# mainboard-augmented-thermostat-v1.net
KiCad netlist of a schematic drawn in EAGLE
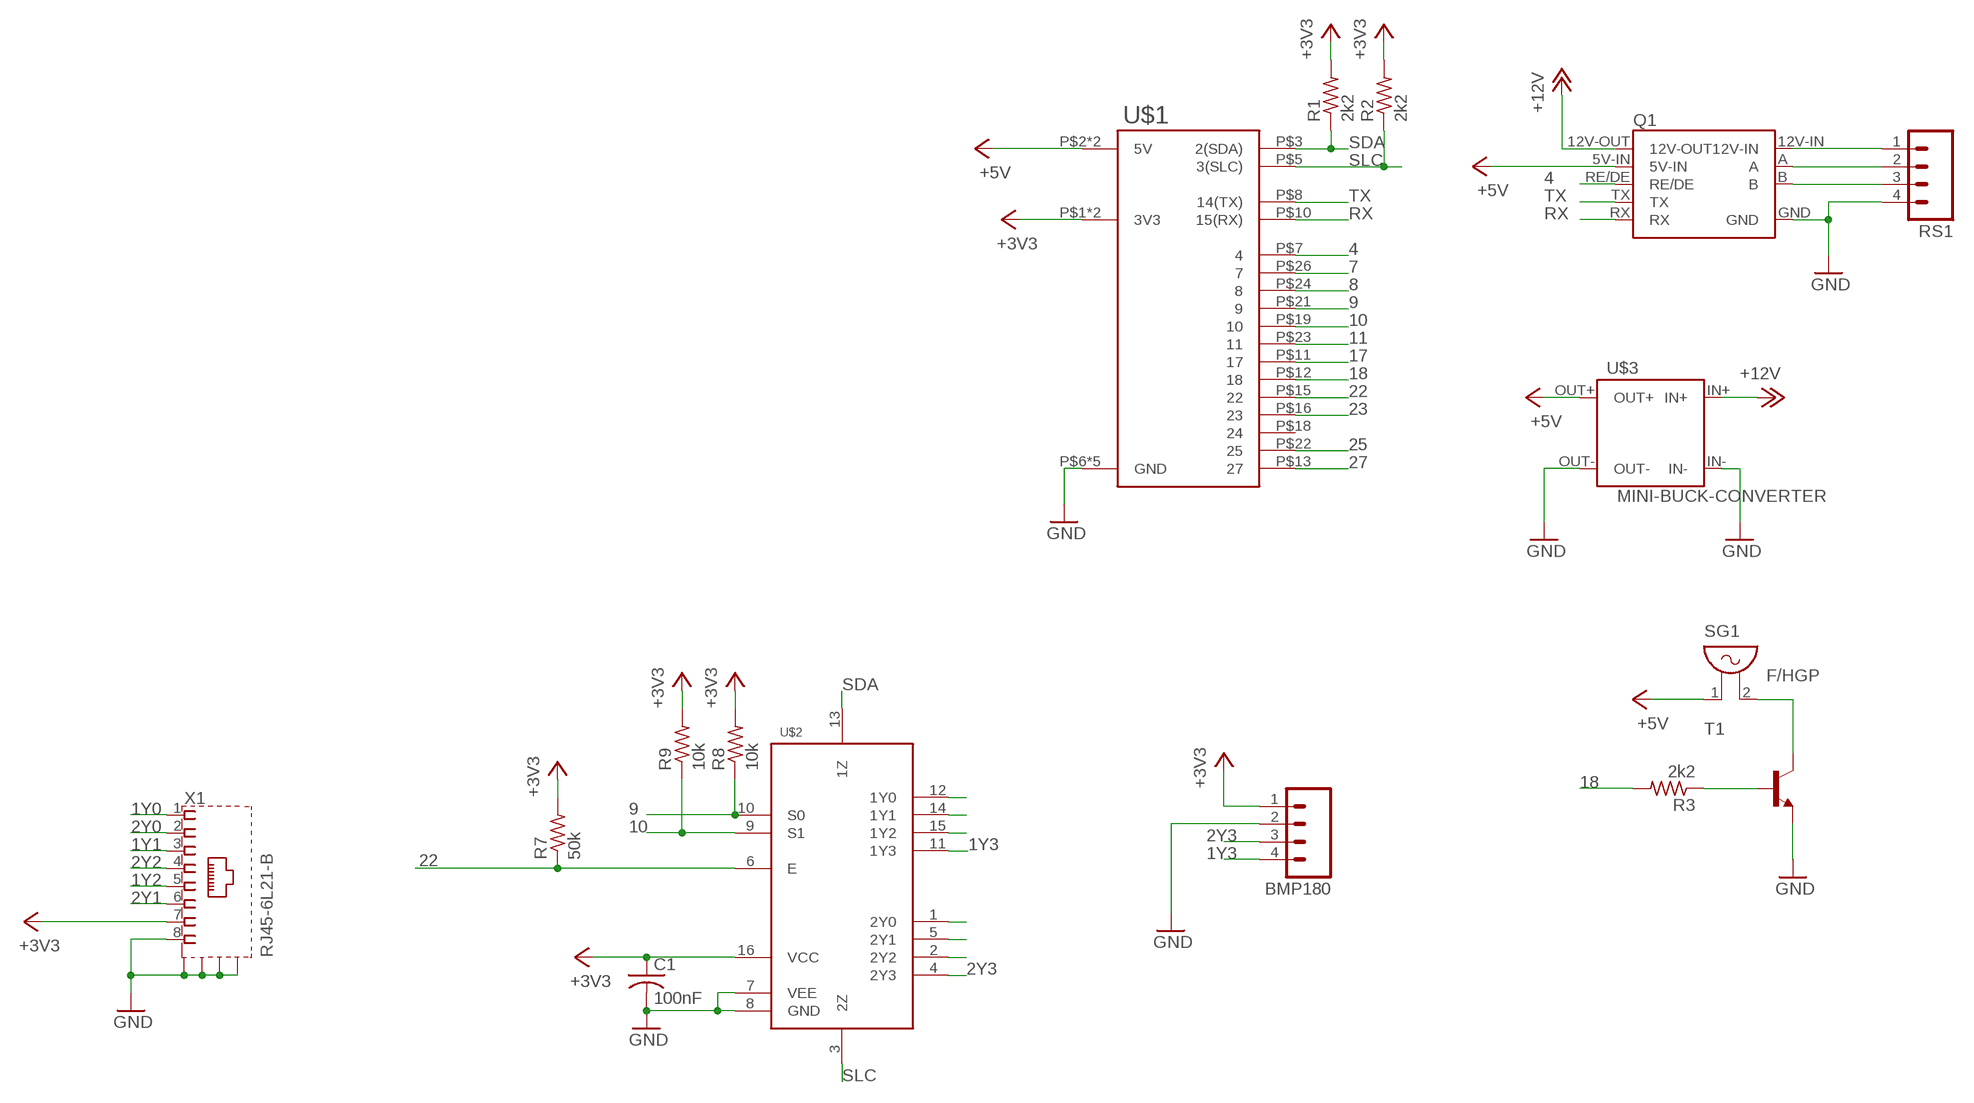
[diagram p0: schematic, sheet 1]

(export (version "E")
  (design (tool "Eeschema 10.0.6"))
  (components
    (comp (ref "BMP180")
      (value "M04")
      (footprint "eagle-import:04P")
      (libsource (lib "eagle-import") (part "M04"))
    )
    (comp (ref "C1")
      (value "100nF")
      (footprint "eagle-import:C0603K")
      (libsource (lib "eagle-import") (part "C-USC0603K"))
    )
    (comp (ref "Q1")
      (value "RS485-ADAPTER0.05-CONNECTOR")
      (footprint "eagle-import:RS485-ADAPTOR-05")
      (libsource (lib "eagle-import") (part "RS485-ADAPTER0.05-CONNECTOR"))
    )
    (comp (ref "R1")
      (value "2k2")
      (footprint "eagle-import:R0603")
      (libsource (lib "eagle-import") (part "R-US_R0603"))
    )
    (comp (ref "R2")
      (value "2k2")
      (footprint "eagle-import:R0603")
      (libsource (lib "eagle-import") (part "R-US_R0603"))
    )
    (comp (ref "R3")
      (value "2k2")
      (footprint "eagle-import:R0603")
      (libsource (lib "eagle-import") (part "R-US_R0603"))
    )
    (comp (ref "R7")
      (value "50k")
      (footprint "eagle-import:R0603")
      (libsource (lib "eagle-import") (part "R-US_R0603"))
    )
    (comp (ref "R8")
      (value "10k")
      (footprint "eagle-import:R0603")
      (libsource (lib "eagle-import") (part "R-US_R0603"))
    )
    (comp (ref "R9")
      (value "10k")
      (footprint "eagle-import:R0603")
      (libsource (lib "eagle-import") (part "R-US_R0603"))
    )
    (comp (ref "RS1")
      (value "M04")
      (footprint "eagle-import:04P")
      (libsource (lib "eagle-import") (part "M04"))
    )
    (comp (ref "SG1")
      (value "F/HGP")
      (footprint "eagle-import:F_HGP")
      (libsource (lib "eagle-import") (part "F/HGP"))
    )
    (comp (ref "T1")
      (value "BC808-NPN-SOT23-BEC")
      (footprint "eagle-import:SOT23-BEC")
      (libsource (lib "eagle-import") (part "-NPN-SOT23-BECBC808"))
    )
    (comp (ref "U$1")
      (value "RASPI-GPIO")
      (footprint "eagle-import:RASPI-GPIO-1")
      (libsource (lib "eagle-import") (part "RASPI-GPIO"))
    )
    (comp (ref "U$2")
      (value "74HC4052SO-16")
      (footprint "eagle-import:SO16")
      (libsource (lib "eagle-import") (part "74HC4052SO-16"))
    )
    (comp (ref "U$3")
      (value "MINI-BUCK-CONVERTER")
      (footprint "eagle-import:MINI-BUCK-CONVERTER")
      (libsource (lib "eagle-import") (part "MINI-BUCK-CONVERTER"))
    )
    (comp (ref "X1")
      (value "RJ45-6L21-B")
      (footprint "eagle-import:RJ45-SHIELD1")
      (libsource (lib "eagle-import") (part "RJ4521-B-6L"))
    )
  )
  (nets
    (net (code "1") (name "+3V3") (class "Default")
      (node (ref "BMP180") (pin "1") (pinfunction "1_1") (pintype "passive"))
      (node (ref "C1") (pin "1") (pinfunction "1_1") (pintype "passive"))
      (node (ref "R1") (pin "2") (pinfunction "2_2") (pintype "passive"))
      (node (ref "R2") (pin "2") (pinfunction "2_2") (pintype "passive"))
      (node (ref "R7") (pin "2") (pinfunction "2_2") (pintype "passive"))
      (node (ref "R8") (pin "2") (pinfunction "2_2") (pintype "passive"))
      (node (ref "R9") (pin "2") (pinfunction "2_2") (pintype "passive"))
      (node (ref "U$1") (pin "P$1") (pinfunction "3V3_P$1") (pintype "power_in"))
      (node (ref "U$1") (pin "P$17") (pinfunction "3V3_P$17") (pintype "power_in"))
      (node (ref "U$2") (pin "16") (pinfunction "VCC_16") (pintype "power_in"))
      (node (ref "X1") (pin "7") (pinfunction "7_7") (pintype "passive"))
    )
    (net (code "2") (name "+5V") (class "Default")
      (node (ref "Q1") (pin "5V-IN") (pinfunction "5V-IN_5V-IN") (pintype "power_in"))
      (node (ref "SG1") (pin "1") (pinfunction "1_1") (pintype "passive"))
      (node (ref "U$1") (pin "P$2") (pinfunction "5V_P$2") (pintype "power_in"))
      (node (ref "U$1") (pin "P$4") (pinfunction "5V_P$4") (pintype "power_in"))
      (node (ref "U$3") (pin "OUT+") (pinfunction "OUT+_OUT+") (pintype "power_in"))
    )
    (net (code "3") (name "+12V") (class "Default")
      (node (ref "Q1") (pin "12V-OUT") (pinfunction "12V-OUT_12V-OUT") (pintype "power_in"))
      (node (ref "U$3") (pin "IN+") (pinfunction "IN+_IN+") (pintype "power_in"))
    )
    (net (code "4") (name "/1Y0") (class "Default")
      (node (ref "U$2") (pin "12") (pinfunction "1Y0_12") (pintype "bidirectional"))
      (node (ref "X1") (pin "1") (pinfunction "1_1") (pintype "passive"))
    )
    (net (code "5") (name "/1Y1") (class "Default")
      (node (ref "U$2") (pin "14") (pinfunction "1Y1_14") (pintype "bidirectional"))
      (node (ref "X1") (pin "3") (pinfunction "3_3") (pintype "passive"))
    )
    (net (code "6") (name "/1Y2") (class "Default")
      (node (ref "U$2") (pin "15") (pinfunction "1Y2_15") (pintype "bidirectional"))
      (node (ref "X1") (pin "5") (pinfunction "5_5") (pintype "passive"))
    )
    (net (code "7") (name "/1Y3") (class "Default")
      (node (ref "BMP180") (pin "4") (pinfunction "4_4") (pintype "passive"))
      (node (ref "U$2") (pin "11") (pinfunction "1Y3_11") (pintype "bidirectional"))
    )
    (net (code "8") (name "/2Y0") (class "Default")
      (node (ref "U$2") (pin "1") (pinfunction "2Y0_1") (pintype "bidirectional"))
      (node (ref "X1") (pin "2") (pinfunction "2_2") (pintype "passive"))
    )
    (net (code "9") (name "/2Y1") (class "Default")
      (node (ref "U$2") (pin "5") (pinfunction "2Y1_5") (pintype "bidirectional"))
      (node (ref "X1") (pin "6") (pinfunction "6_6") (pintype "passive"))
    )
    (net (code "10") (name "/2Y2") (class "Default")
      (node (ref "U$2") (pin "2") (pinfunction "2Y2_2") (pintype "bidirectional"))
      (node (ref "X1") (pin "4") (pinfunction "4_4") (pintype "passive"))
    )
    (net (code "11") (name "/2Y3") (class "Default")
      (node (ref "BMP180") (pin "3") (pinfunction "3_3") (pintype "passive"))
      (node (ref "U$2") (pin "4") (pinfunction "2Y3_4") (pintype "bidirectional"))
    )
    (net (code "12") (name "/4") (class "Default")
      (node (ref "Q1") (pin "RE/DE") (pinfunction "RE/DE_RE/DE") (pintype "bidirectional"))
      (node (ref "U$1") (pin "P$7") (pinfunction "4_P$7") (pintype "bidirectional"))
    )
    (net (code "13") (name "/7") (class "Default")
      (node (ref "U$1") (pin "P$26") (pinfunction "7_P$26") (pintype "bidirectional"))
    )
    (net (code "14") (name "/8") (class "Default")
      (node (ref "U$1") (pin "P$24") (pinfunction "8_P$24") (pintype "bidirectional"))
    )
    (net (code "15") (name "/9") (class "Default")
      (node (ref "R8") (pin "1") (pinfunction "1_1") (pintype "passive"))
      (node (ref "U$1") (pin "P$21") (pinfunction "9_P$21") (pintype "bidirectional"))
      (node (ref "U$2") (pin "10") (pinfunction "S0_10") (pintype "bidirectional"))
    )
    (net (code "16") (name "/10") (class "Default")
      (node (ref "R9") (pin "1") (pinfunction "1_1") (pintype "passive"))
      (node (ref "U$1") (pin "P$19") (pinfunction "10_P$19") (pintype "bidirectional"))
      (node (ref "U$2") (pin "9") (pinfunction "S1_9") (pintype "bidirectional"))
    )
    (net (code "17") (name "/11") (class "Default")
      (node (ref "U$1") (pin "P$23") (pinfunction "11_P$23") (pintype "bidirectional"))
    )
    (net (code "18") (name "/17") (class "Default")
      (node (ref "U$1") (pin "P$11") (pinfunction "17_P$11") (pintype "bidirectional"))
    )
    (net (code "19") (name "/18") (class "Default")
      (node (ref "R3") (pin "2") (pinfunction "2_2") (pintype "passive"))
      (node (ref "U$1") (pin "P$12") (pinfunction "18_P$12") (pintype "bidirectional"))
    )
    (net (code "20") (name "/22") (class "Default")
      (node (ref "R7") (pin "1") (pinfunction "1_1") (pintype "passive"))
      (node (ref "U$1") (pin "P$15") (pinfunction "22_P$15") (pintype "bidirectional"))
      (node (ref "U$2") (pin "6") (pinfunction "E_6") (pintype "bidirectional"))
    )
    (net (code "21") (name "/23") (class "Default")
      (node (ref "U$1") (pin "P$16") (pinfunction "23_P$16") (pintype "bidirectional"))
    )
    (net (code "22") (name "/25") (class "Default")
      (node (ref "U$1") (pin "P$22") (pinfunction "25_P$22") (pintype "bidirectional"))
    )
    (net (code "23") (name "/27") (class "Default")
      (node (ref "U$1") (pin "P$13") (pinfunction "27_P$13") (pintype "bidirectional"))
    )
    (net (code "24") (name "/RX") (class "Default")
      (node (ref "Q1") (pin "RX") (pinfunction "RX_RX") (pintype "bidirectional"))
      (node (ref "U$1") (pin "P$10") (pinfunction "15(RX)_P$10") (pintype "bidirectional"))
    )
    (net (code "25") (name "/SDA") (class "Default")
      (node (ref "R1") (pin "1") (pinfunction "1_1") (pintype "passive"))
      (node (ref "U$1") (pin "P$3") (pinfunction "2(SDA)_P$3") (pintype "bidirectional"))
      (node (ref "U$2") (pin "13") (pinfunction "1Z_13") (pintype "input"))
    )
    (net (code "26") (name "/SLC") (class "Default")
      (node (ref "R2") (pin "1") (pinfunction "1_1") (pintype "passive"))
      (node (ref "U$1") (pin "P$5") (pinfunction "3(SLC)_P$5") (pintype "bidirectional"))
      (node (ref "U$2") (pin "3") (pinfunction "2Z_3") (pintype "output"))
    )
    (net (code "27") (name "/TX") (class "Default")
      (node (ref "Q1") (pin "TX") (pinfunction "TX_TX") (pintype "bidirectional"))
      (node (ref "U$1") (pin "P$8") (pinfunction "14(TX)_P$8") (pintype "bidirectional"))
    )
    (net (code "28") (name "GND") (class "Default")
      (node (ref "BMP180") (pin "2") (pinfunction "2_2") (pintype "passive"))
      (node (ref "C1") (pin "2") (pinfunction "2_2") (pintype "passive"))
      (node (ref "Q1") (pin "GND") (pinfunction "GND_GND") (pintype "power_in"))
      (node (ref "RS1") (pin "4") (pinfunction "4_4") (pintype "passive"))
      (node (ref "T1") (pin "E") (pinfunction "E_E") (pintype "passive"))
      (node (ref "U$1") (pin "P$14") (pinfunction "GND_P$14") (pintype "power_in"))
      (node (ref "U$1") (pin "P$20") (pinfunction "GND_P$20") (pintype "power_in"))
      (node (ref "U$1") (pin "P$25") (pinfunction "GND_P$25") (pintype "power_in"))
      (node (ref "U$1") (pin "P$6") (pinfunction "GND_P$6") (pintype "power_in"))
      (node (ref "U$1") (pin "P$9") (pinfunction "GND_P$9") (pintype "power_in"))
      (node (ref "U$2") (pin "7") (pinfunction "VEE_7") (pintype "power_in"))
      (node (ref "U$2") (pin "8") (pinfunction "GND_8") (pintype "power_in"))
      (node (ref "U$3") (pin "IN-") (pinfunction "IN-_IN-") (pintype "power_in"))
      (node (ref "U$3") (pin "OUT-") (pinfunction "OUT-_OUT-") (pintype "power_in"))
      (node (ref "X1") (pin "8") (pinfunction "8_8") (pintype "passive"))
      (node (ref "X1") (pin "S1") (pinfunction "S_S1") (pintype "passive"))
      (node (ref "X1") (pin "S2") (pinfunction "S_S2") (pintype "passive"))
      (node (ref "X1") (pin "S3") (pinfunction "S_S3") (pintype "passive"))
      (node (ref "X1") (pin "S4") (pinfunction "S_S4") (pintype "passive"))
    )
    (net (code "29") (name "Net-(Q1-Pad12V-IN)") (class "Default")
      (node (ref "Q1") (pin "12V-IN") (pinfunction "12V-IN_12V-IN") (pintype "power_in"))
      (node (ref "RS1") (pin "1") (pinfunction "1_1") (pintype "passive"))
    )
    (net (code "30") (name "Net-(Q1-PadA)") (class "Default")
      (node (ref "Q1") (pin "A") (pinfunction "A_A") (pintype "bidirectional"))
      (node (ref "RS1") (pin "2") (pinfunction "2_2") (pintype "passive"))
    )
    (net (code "31") (name "Net-(Q1-PadB)") (class "Default")
      (node (ref "Q1") (pin "B") (pinfunction "B_B") (pintype "bidirectional"))
      (node (ref "RS1") (pin "3") (pinfunction "3_3") (pintype "passive"))
    )
    (net (code "32") (name "Net-(R3-Pad1)") (class "Default")
      (node (ref "R3") (pin "1") (pinfunction "1_1") (pintype "passive"))
      (node (ref "T1") (pin "B") (pinfunction "B_B") (pintype "passive"))
    )
    (net (code "33") (name "Net-(SG1-Pad2)") (class "Default")
      (node (ref "SG1") (pin "2") (pinfunction "2_2") (pintype "passive"))
      (node (ref "T1") (pin "C") (pinfunction "C_C") (pintype "passive"))
    )
    (net (code "34") (name "unconnected-(U$1-24-PadP$18)") (class "Default")
      (node (ref "U$1") (pin "P$18") (pinfunction "24_P$18") (pintype "bidirectional"))
    )
  )
)
